# Yam_Thwoll_Ommo.net
KiCad netlist of a schematic drawn in EAGLE
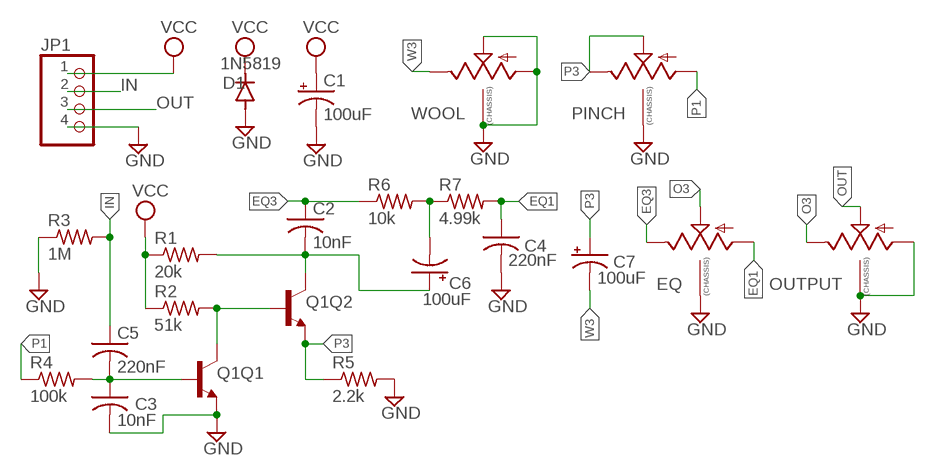
[diagram p0: schematic, sheet 1]

(export (version "E")
  (design (tool "Eeschema 10.0.6"))
  (components
    (comp (ref "C1")
      (value "100uF")
      (footprint "eagle-import:PAN_B_SMD+THRU")
      (libsource (lib "eagle-import") (part "CAP_SMD+THRUPAN_B"))
    )
    (comp (ref "C2")
      (value "10nF")
      (footprint "eagle-import:C0402")
      (libsource (lib "eagle-import") (part "C-USC0402"))
    )
    (comp (ref "C3")
      (value "10nF")
      (footprint "eagle-import:C0402")
      (libsource (lib "eagle-import") (part "C-USC0402"))
    )
    (comp (ref "C4")
      (value "220nF")
      (footprint "eagle-import:C0402")
      (libsource (lib "eagle-import") (part "C-USC0402"))
    )
    (comp (ref "C5")
      (value "220nF")
      (footprint "eagle-import:C0402")
      (libsource (lib "eagle-import") (part "C-USC0402"))
    )
    (comp (ref "C6")
      (value "100uF")
      (footprint "eagle-import:PAN_B_SMD+THRU")
      (libsource (lib "eagle-import") (part "CAP_SMD+THRUPAN_B"))
    )
    (comp (ref "C7")
      (value "100uF")
      (footprint "eagle-import:PAN_B_SMD+THRU")
      (libsource (lib "eagle-import") (part "CAP_SMD+THRUPAN_B"))
    )
    (comp (ref "D1")
      (value "1N5819")
      (footprint "eagle-import:SOD123")
      (libsource (lib "eagle-import") (part "DIODE-SOD123"))
    )
    (comp (ref "EQ")
      (value "9MM_SNAP-IN_POT_CHASSIS")
      (footprint "eagle-import:9MM_SNAP-IN_POT")
      (libsource (lib "eagle-import") (part "9MM_SNAP-IN_POT_CHASSIS"))
    )
    (comp (ref "JP1")
      (value "PINHD-1X4")
      (footprint "eagle-import:1X04")
      (libsource (lib "eagle-import") (part "PINHD-1X4"))
    )
    (comp (ref "OUTPUT")
      (value "9MM_SNAP-IN_POT_CHASSIS")
      (footprint "eagle-import:9MM_SNAP-IN_POT")
      (libsource (lib "eagle-import") (part "9MM_SNAP-IN_POT_CHASSIS"))
    )
    (comp (ref "PINCH")
      (value "9MM_SNAP-IN_POT_CHASSIS")
      (footprint "eagle-import:9MM_SNAP-IN_POT")
      (libsource (lib "eagle-import") (part "9MM_SNAP-IN_POT_CHASSIS"))
    )
    (comp (ref "Q1")
      (value "TRANS_NPN_DUAL-MBT3904DW1T1")
      (footprint "eagle-import:SC70-6")
      (libsource (lib "eagle-import") (part "TRANS_NPN_DUAL-MBT3904DW1T1"))
    )
    (comp (ref "R1")
      (value "20k")
      (footprint "eagle-import:R0402")
      (libsource (lib "eagle-import") (part "R-US_R0402"))
    )
    (comp (ref "R2")
      (value "51k")
      (footprint "eagle-import:R0402")
      (libsource (lib "eagle-import") (part "R-US_R0402"))
    )
    (comp (ref "R3")
      (value "1M")
      (footprint "eagle-import:R0402")
      (libsource (lib "eagle-import") (part "R-US_R0402"))
    )
    (comp (ref "R4")
      (value "100k")
      (footprint "eagle-import:R0402")
      (libsource (lib "eagle-import") (part "R-US_R0402"))
    )
    (comp (ref "R5")
      (value "2.2k")
      (footprint "eagle-import:R0402")
      (libsource (lib "eagle-import") (part "R-US_R0402"))
    )
    (comp (ref "R6")
      (value "10k")
      (footprint "eagle-import:R0402")
      (libsource (lib "eagle-import") (part "R-US_R0402"))
    )
    (comp (ref "R7")
      (value "4.99k")
      (footprint "eagle-import:R0402")
      (libsource (lib "eagle-import") (part "R-US_R0402"))
    )
    (comp (ref "WOOL")
      (value "9MM_SNAP-IN_POT_CHASSIS")
      (footprint "eagle-import:9MM_SNAP-IN_POT")
      (libsource (lib "eagle-import") (part "9MM_SNAP-IN_POT_CHASSIS"))
    )
  )
  (nets
    (net (code "1") (name "EQ1") (class "Default")
      (node (ref "C4") (pin "1") (pinfunction "1_1") (pintype "passive"))
      (node (ref "EQ") (pin "1") (pinfunction "A_1") (pintype "passive"))
      (node (ref "R7") (pin "2") (pinfunction "2_2") (pintype "passive"))
    )
    (net (code "2") (name "EQ3") (class "Default")
      (node (ref "C2") (pin "1") (pinfunction "1_1") (pintype "passive"))
      (node (ref "EQ") (pin "3") (pinfunction "E_3") (pintype "passive"))
      (node (ref "R6") (pin "1") (pinfunction "1_1") (pintype "passive"))
    )
    (net (code "3") (name "GND") (class "Default")
      (node (ref "C1") (pin "-") (pinfunction "-_-") (pintype "passive"))
      (node (ref "C1") (pin "--") (pinfunction "-_--") (pintype "passive"))
      (node (ref "C3") (pin "2") (pinfunction "2_2") (pintype "passive"))
      (node (ref "C4") (pin "2") (pinfunction "2_2") (pintype "passive"))
      (node (ref "D1") (pin "A") (pinfunction "A_A") (pintype "passive"))
      (node (ref "EQ") (pin "CHASSIS1") (pinfunction "P$1_CHASSIS1") (pintype "passive"))
      (node (ref "EQ") (pin "CHASSIS2") (pinfunction "P$1_CHASSIS2") (pintype "passive"))
      (node (ref "JP1") (pin "4") (pinfunction "4_4") (pintype "passive"))
      (node (ref "OUTPUT") (pin "1") (pinfunction "A_1") (pintype "passive"))
      (node (ref "OUTPUT") (pin "CHASSIS1") (pinfunction "P$1_CHASSIS1") (pintype "passive"))
      (node (ref "OUTPUT") (pin "CHASSIS2") (pinfunction "P$1_CHASSIS2") (pintype "passive"))
      (node (ref "PINCH") (pin "CHASSIS1") (pinfunction "P$1_CHASSIS1") (pintype "passive"))
      (node (ref "PINCH") (pin "CHASSIS2") (pinfunction "P$1_CHASSIS2") (pintype "passive"))
      (node (ref "Q1") (pin "4") (pinfunction "E_4") (pintype "passive"))
      (node (ref "R3") (pin "1") (pinfunction "1_1") (pintype "passive"))
      (node (ref "R5") (pin "2") (pinfunction "2_2") (pintype "passive"))
      (node (ref "WOOL") (pin "1") (pinfunction "A_1") (pintype "passive"))
      (node (ref "WOOL") (pin "2") (pinfunction "S_2") (pintype "passive"))
      (node (ref "WOOL") (pin "CHASSIS1") (pinfunction "P$1_CHASSIS1") (pintype "passive"))
      (node (ref "WOOL") (pin "CHASSIS2") (pinfunction "P$1_CHASSIS2") (pintype "passive"))
    )
    (net (code "4") (name "IN") (class "Default")
      (node (ref "C5") (pin "1") (pinfunction "1_1") (pintype "passive"))
      (node (ref "JP1") (pin "2") (pinfunction "2_2") (pintype "passive"))
      (node (ref "R3") (pin "2") (pinfunction "2_2") (pintype "passive"))
    )
    (net (code "5") (name "Net-(C6---Pad--)") (class "Default")
      (node (ref "C6") (pin "-") (pinfunction "-_-") (pintype "passive"))
      (node (ref "C6") (pin "--") (pinfunction "-_--") (pintype "passive"))
      (node (ref "R6") (pin "2") (pinfunction "2_2") (pintype "passive"))
      (node (ref "R7") (pin "1") (pinfunction "1_1") (pintype "passive"))
    )
    (net (code "6") (name "Net-(Q1A-B)") (class "Default")
      (node (ref "C3") (pin "1") (pinfunction "1_1") (pintype "passive"))
      (node (ref "C5") (pin "2") (pinfunction "2_2") (pintype "passive"))
      (node (ref "Q1") (pin "5") (pinfunction "B_5") (pintype "passive"))
      (node (ref "R4") (pin "2") (pinfunction "2_2") (pintype "passive"))
    )
    (net (code "7") (name "Net-(Q1A-C)") (class "Default")
      (node (ref "Q1") (pin "2") (pinfunction "B_2") (pintype "passive"))
      (node (ref "Q1") (pin "3") (pinfunction "C_3") (pintype "passive"))
      (node (ref "R2") (pin "2") (pinfunction "2_2") (pintype "passive"))
    )
    (net (code "8") (name "Net-(Q1B-C)") (class "Default")
      (node (ref "C2") (pin "2") (pinfunction "2_2") (pintype "passive"))
      (node (ref "C6") (pin "+") (pinfunction "+_+") (pintype "passive"))
      (node (ref "C6") (pin "++") (pinfunction "+_++") (pintype "passive"))
      (node (ref "Q1") (pin "6") (pinfunction "C_6") (pintype "passive"))
      (node (ref "R1") (pin "2") (pinfunction "2_2") (pintype "passive"))
    )
    (net (code "9") (name "O3") (class "Default")
      (node (ref "EQ") (pin "2") (pinfunction "S_2") (pintype "passive"))
      (node (ref "OUTPUT") (pin "3") (pinfunction "E_3") (pintype "passive"))
    )
    (net (code "10") (name "OUT") (class "Default")
      (node (ref "JP1") (pin "3") (pinfunction "3_3") (pintype "passive"))
      (node (ref "OUTPUT") (pin "2") (pinfunction "S_2") (pintype "passive"))
    )
    (net (code "11") (name "P1") (class "Default")
      (node (ref "PINCH") (pin "1") (pinfunction "A_1") (pintype "passive"))
      (node (ref "R4") (pin "1") (pinfunction "1_1") (pintype "passive"))
    )
    (net (code "12") (name "P3") (class "Default")
      (node (ref "C7") (pin "+") (pinfunction "+_+") (pintype "passive"))
      (node (ref "C7") (pin "++") (pinfunction "+_++") (pintype "passive"))
      (node (ref "PINCH") (pin "2") (pinfunction "S_2") (pintype "passive"))
      (node (ref "PINCH") (pin "3") (pinfunction "E_3") (pintype "passive"))
      (node (ref "Q1") (pin "1") (pinfunction "E_1") (pintype "passive"))
      (node (ref "R5") (pin "1") (pinfunction "1_1") (pintype "passive"))
    )
    (net (code "13") (name "VCC") (class "Default")
      (node (ref "C1") (pin "+") (pinfunction "+_+") (pintype "passive"))
      (node (ref "C1") (pin "++") (pinfunction "+_++") (pintype "passive"))
      (node (ref "D1") (pin "C") (pinfunction "C_C") (pintype "passive"))
      (node (ref "JP1") (pin "1") (pinfunction "1_1") (pintype "passive"))
      (node (ref "R1") (pin "1") (pinfunction "1_1") (pintype "passive"))
      (node (ref "R2") (pin "1") (pinfunction "1_1") (pintype "passive"))
    )
    (net (code "14") (name "W3") (class "Default")
      (node (ref "C7") (pin "-") (pinfunction "-_-") (pintype "passive"))
      (node (ref "C7") (pin "--") (pinfunction "-_--") (pintype "passive"))
      (node (ref "WOOL") (pin "3") (pinfunction "E_3") (pintype "passive"))
    )
  )
)
